# mp3412-boost-driver-17mm-mk-1_1.net
KiCad netlist of a schematic drawn in EAGLE
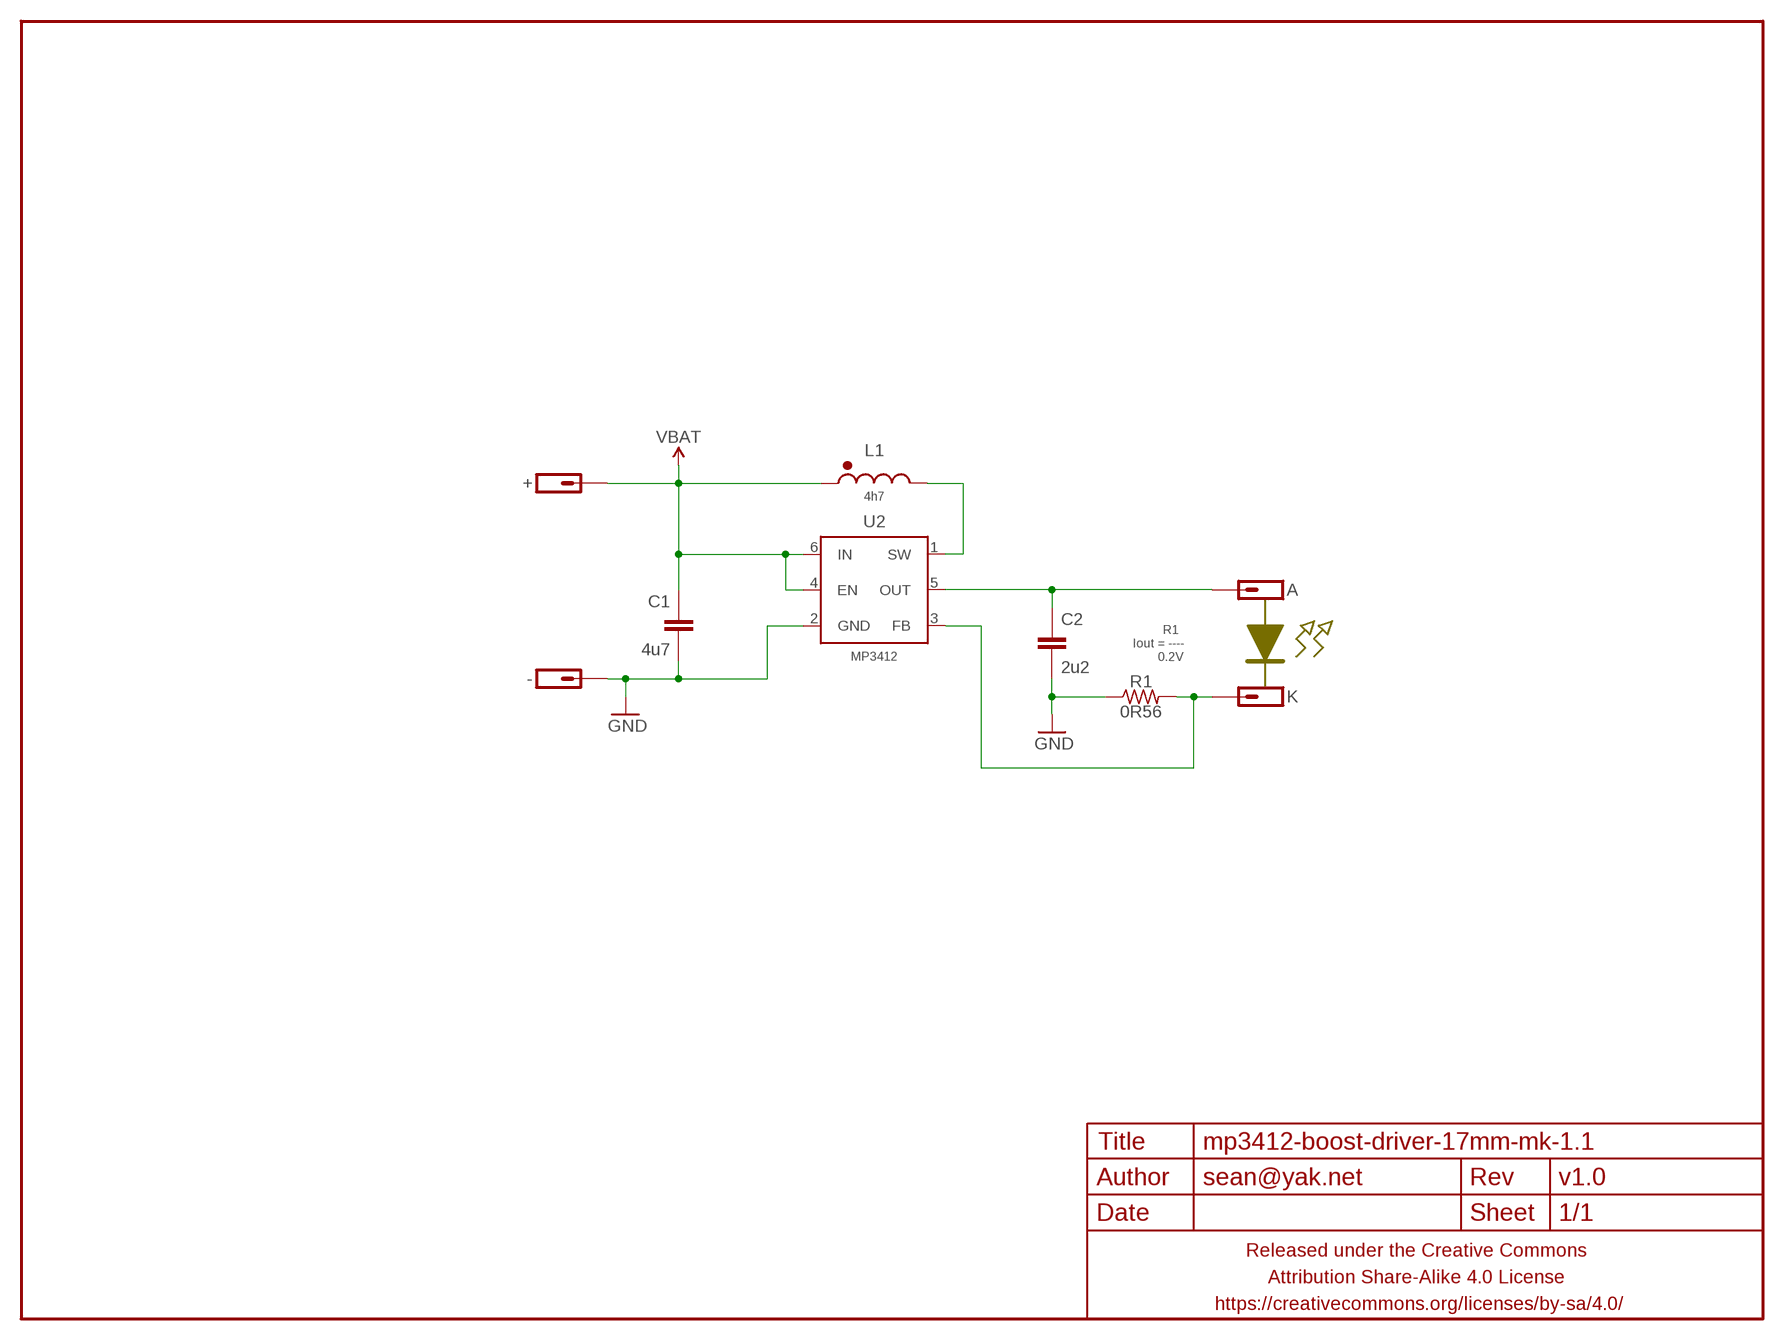
[diagram p0: schematic, sheet 1]

(export (version "E")
  (design (tool "Eeschema 10.0.6"))
  (components
    (comp (ref "+")
      (value "M01NOT-A-VIA-NOPE")
      (footprint "eagle-import:1X01_NOSILK_NOSTOP")
      (libsource (lib "eagle-import") (part "M01NOT-A-VIA-NOPE"))
    )
    (comp (ref "-")
      (value "M01NOT-A-VIA-NOPE")
      (footprint "eagle-import:1X01_NOSILK_NOSTOP")
      (libsource (lib "eagle-import") (part "M01NOT-A-VIA-NOPE"))
    )
    (comp (ref "A")
      (value "M01PTH-1MM-CIR-NS")
      (footprint "eagle-import:1X01-1MM-CIR-NS")
      (libsource (lib "eagle-import") (part "M01PTH-1MM-CIR-NS"))
    )
    (comp (ref "C1")
      (value "4u7")
      (footprint "eagle-import:C0603-TIGHTER")
      (libsource (lib "eagle-import") (part "CAPACITOR-CERAMICC0603-TIGHTER"))
    )
    (comp (ref "C2")
      (value "2u2")
      (footprint "eagle-import:C0603-TIGHTER")
      (libsource (lib "eagle-import") (part "CAPACITOR-CERAMICC0603-TIGHTER"))
    )
    (comp (ref "FRAME1")
      (value "FRAME-LETTERNO_PACKAGE")
      (footprint "eagle-import:DUMMY")
      (fields (field (name "DESIGNER") "sean@yak.net") (field (name "VERSION") "v1.0"))
      (libsource (lib "eagle-import") (part "FRAME-LETTERNO_PACKAGE"))
    )
    (comp (ref "K")
      (value "M01PTH-1MM-CIR-NS")
      (footprint "eagle-import:1X01-1MM-CIR-NS")
      (libsource (lib "eagle-import") (part "M01PTH-1MM-CIR-NS"))
    )
    (comp (ref "L1")
      (value "4h7")
      (footprint "eagle-import:EPL2014")
      (libsource (lib "eagle-import") (part "INDUCTOREPL2014"))
    )
    (comp (ref "R1")
      (value "0R56")
      (footprint "eagle-import:R0603-TIGHTER")
      (libsource (lib "eagle-import") (part "RESISTORR0603-TIGHTER"))
    )
    (comp (ref "U2")
      (value "MP3412")
      (footprint "eagle-import:TSOT-23-6")
      (libsource (lib "eagle-import") (part "MP3412"))
    )
  )
  (nets
    (net (code "1") (name "GND") (class "Default")
      (node (ref "-") (pin "P$1") (pinfunction "1_P$1") (pintype "passive"))
      (node (ref "C1") (pin "2") (pinfunction "2_2") (pintype "passive"))
      (node (ref "C2") (pin "2") (pinfunction "2_2") (pintype "passive"))
      (node (ref "R1") (pin "1") (pinfunction "1_1") (pintype "passive"))
      (node (ref "U2") (pin "2") (pinfunction "GND_2") (pintype "bidirectional"))
    )
    (net (code "2") (name "Net-(L1-2)") (class "Default")
      (node (ref "L1") (pin "P$2") (pinfunction "2_P$2") (pintype "passive"))
      (node (ref "U2") (pin "1") (pinfunction "SW_1") (pintype "bidirectional"))
    )
    (net (code "3") (name "Net-(U2-FB)") (class "Default")
      (node (ref "K") (pin "1") (pinfunction "1_1") (pintype "passive"))
      (node (ref "R1") (pin "2") (pinfunction "2_2") (pintype "passive"))
      (node (ref "U2") (pin "3") (pinfunction "FB_3") (pintype "bidirectional"))
    )
    (net (code "4") (name "Net-(U2-OUT)") (class "Default")
      (node (ref "A") (pin "1") (pinfunction "1_1") (pintype "passive"))
      (node (ref "C2") (pin "1") (pinfunction "1_1") (pintype "passive"))
      (node (ref "U2") (pin "5") (pinfunction "OUT_5") (pintype "bidirectional"))
    )
    (net (code "5") (name "VBAT") (class "Default")
      (node (ref "+") (pin "P$1") (pinfunction "1_P$1") (pintype "passive"))
      (node (ref "C1") (pin "1") (pinfunction "1_1") (pintype "passive"))
      (node (ref "L1") (pin "P$1") (pinfunction "1_P$1") (pintype "passive"))
      (node (ref "U2") (pin "4") (pinfunction "EN_4") (pintype "bidirectional"))
      (node (ref "U2") (pin "6") (pinfunction "IN_6") (pintype "bidirectional"))
    )
  )
)
